# muff-pi-clone.net
KiCad netlist of a schematic drawn in EAGLE
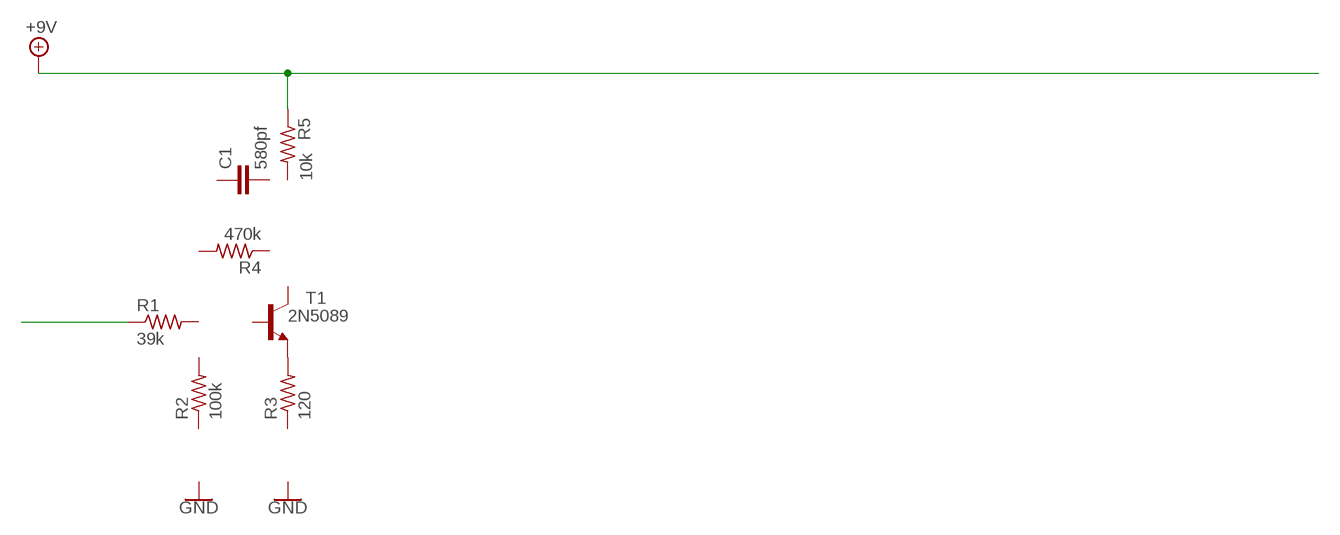
[diagram p0: schematic, sheet 1]

(export (version "E")
  (design (tool "Eeschema 10.0.6"))
  (components
    (comp (ref "C1")
      (value "580pf")
      (footprint "eagle-import:C025-030X050")
      (libsource (lib "eagle-import") (part "C-EU025-030X050"))
    )
    (comp (ref "R1")
      (value "39k")
      (footprint "eagle-import:0204_7")
      (libsource (lib "eagle-import") (part "R-US_0204/7"))
    )
    (comp (ref "R2")
      (value "100k")
      (footprint "eagle-import:0204_7")
      (libsource (lib "eagle-import") (part "R-US_0204/7"))
    )
    (comp (ref "R3")
      (value "120")
      (footprint "eagle-import:0204_7")
      (libsource (lib "eagle-import") (part "R-US_0204/7"))
    )
    (comp (ref "R4")
      (value "470k")
      (footprint "eagle-import:0204_7")
      (libsource (lib "eagle-import") (part "R-US_0204/7"))
    )
    (comp (ref "R5")
      (value "10k")
      (footprint "eagle-import:0204_7")
      (libsource (lib "eagle-import") (part "R-US_0204/7"))
    )
    (comp (ref "T1")
      (value "2N5089")
      (footprint "eagle-import:TO92")
      (libsource (lib "eagle-import") (part "2N5089"))
    )
  )
  (nets
    (net (code "1") (name "+9V") (class "Default")
      (node (ref "R5") (pin "1") (pinfunction "1_1") (pintype "passive"))
    )
    (net (code "3") (name "Net-(T1-E)") (class "Default")
      (node (ref "R3") (pin "2") (pinfunction "2_2") (pintype "passive"))
      (node (ref "T1") (pin "3") (pinfunction "E_3") (pintype "passive"))
    )
    (net (code "4") (name "unconnected-(C1-Pad1)") (class "Default")
      (node (ref "C1") (pin "1") (pinfunction "1_1") (pintype "passive"))
    )
    (net (code "5") (name "unconnected-(C1-Pad2)") (class "Default")
      (node (ref "C1") (pin "2") (pinfunction "2_2") (pintype "passive"))
    )
    (net (code "6") (name "unconnected-(R1-Pad1)") (class "Default")
      (node (ref "R1") (pin "1") (pinfunction "1_1") (pintype "passive"))
    )
    (net (code "7") (name "unconnected-(R1-Pad2)") (class "Default")
      (node (ref "R1") (pin "2") (pinfunction "2_2") (pintype "passive"))
    )
    (net (code "8") (name "unconnected-(R2-Pad1)") (class "Default")
      (node (ref "R2") (pin "1") (pinfunction "1_1") (pintype "passive"))
    )
    (net (code "9") (name "unconnected-(R2-Pad2)") (class "Default")
      (node (ref "R2") (pin "2") (pinfunction "2_2") (pintype "passive"))
    )
    (net (code "10") (name "unconnected-(R3-Pad1)") (class "Default")
      (node (ref "R3") (pin "1") (pinfunction "1_1") (pintype "passive"))
    )
    (net (code "11") (name "unconnected-(R4-Pad1)") (class "Default")
      (node (ref "R4") (pin "1") (pinfunction "1_1") (pintype "passive"))
    )
    (net (code "12") (name "unconnected-(R4-Pad2)") (class "Default")
      (node (ref "R4") (pin "2") (pinfunction "2_2") (pintype "passive"))
    )
    (net (code "13") (name "unconnected-(R5-Pad2)") (class "Default")
      (node (ref "R5") (pin "2") (pinfunction "2_2") (pintype "passive"))
    )
    (net (code "14") (name "unconnected-(T1-B-Pad2)") (class "Default")
      (node (ref "T1") (pin "2") (pinfunction "B_2") (pintype "passive"))
    )
    (net (code "15") (name "unconnected-(T1-C-Pad1)") (class "Default")
      (node (ref "T1") (pin "1") (pinfunction "C_1") (pintype "passive"))
    )
  )
)
